# Flatcaster-Link-sch.net
KiCad netlist of a schematic drawn in Altium Designer
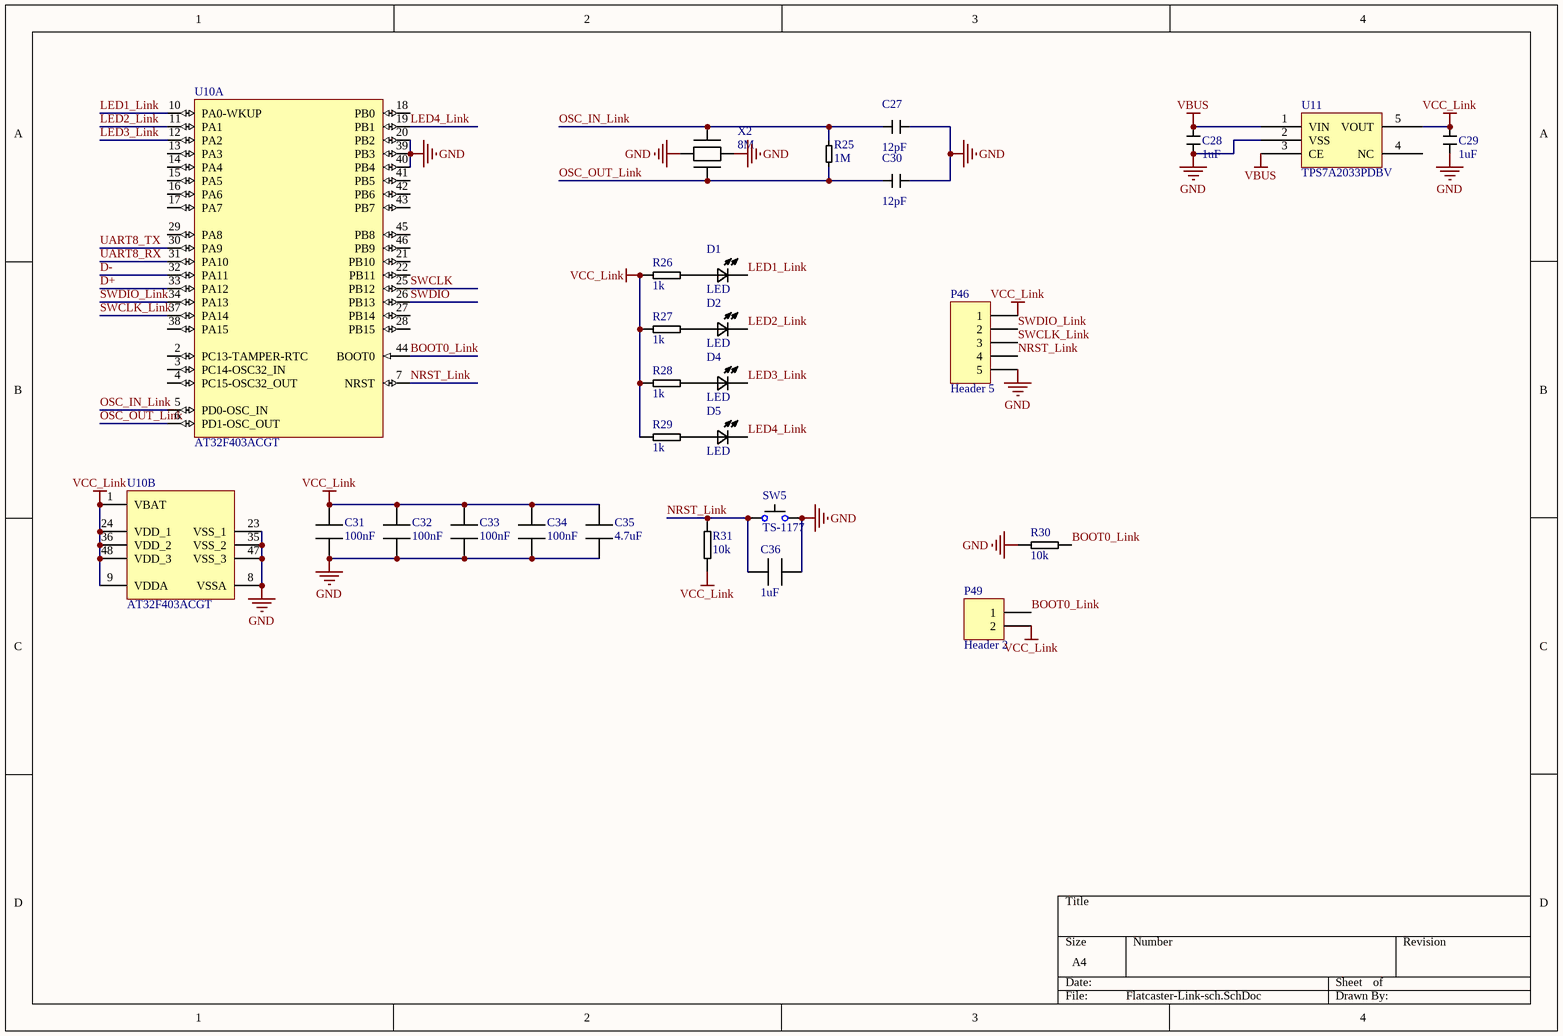
[diagram p0: Flatcaster-Link-sch.SchDoc]

(export (version "E")
  (design (tool "Eeschema 10.0.6"))
  (components
    (comp (ref "C27") (value "12pF") (footprint "0603-Cap") (libsource (lib "") (part "Cap_1")))
    (comp (ref "C28") (value "1uF") (footprint "0603-Cap") (libsource (lib "") (part "Cap_1")))
    (comp (ref "C29") (value "1uF") (footprint "0603-Cap") (libsource (lib "") (part "Cap_1")))
    (comp (ref "C30") (value "12pF") (footprint "0603-Cap") (libsource (lib "") (part "Cap_1")))
    (comp (ref "C31") (value "100nF") (footprint "0603-Cap") (libsource (lib "LibCfrpg") (part "Cap")))
    (comp (ref "C32") (value "100nF") (footprint "0603-Cap") (libsource (lib "LibCfrpg") (part "Cap")))
    (comp (ref "C33") (value "100nF") (footprint "0603-Cap") (libsource (lib "LibCfrpg") (part "Cap")))
    (comp (ref "C34") (value "100nF") (footprint "0603-Cap") (libsource (lib "LibCfrpg") (part "Cap")))
    (comp (ref "C35") (value "4.7uF") (footprint "0603-Cap") (libsource (lib "LibCfrpg") (part "Cap")))
    (comp (ref "C36") (value "1uF") (footprint "0603-Cap") (libsource (lib "LibCfrpg") (part "Cap")))
    (comp (ref "D1") (value "LED") (footprint "0603-1") (libsource (lib "LibCfrpg") (part "LED")))
    (comp (ref "D2") (value "LED") (footprint "0603-1") (libsource (lib "LibCfrpg") (part "LED")))
    (comp (ref "D4") (value "LED") (footprint "0603-1") (libsource (lib "LibCfrpg") (part "LED")))
    (comp (ref "D5") (value "LED") (footprint "0603-1") (libsource (lib "LibCfrpg") (part "LED")))
    (comp (ref "P46")
      (value "Header 5")
      (footprint "HDR1X5")
      (description "Header, 5-Pin")
      (fields (field (name "PUBLISHER") "Altium Limited"))
      (libsource (lib "Miscellaneous Connectors") (part "Header 5"))
    )
    (comp (ref "P49")
      (value "Header 2")
      (footprint "HDR1X2")
      (description "Header, 2-Pin")
      (fields (field (name "PUBLISHER") "Altium Limited"))
      (libsource (lib "Miscellaneous Connectors") (part "Header 2"))
    )
    (comp (ref "R25") (value "1M") (footprint "0603") (libsource (lib "") (part "Res_1")))
    (comp (ref "R26") (value "1k") (footprint "0603") (libsource (lib "LibCfrpg") (part "Res")))
    (comp (ref "R27") (value "1k") (footprint "0603") (libsource (lib "LibCfrpg") (part "Res")))
    (comp (ref "R28") (value "1k") (footprint "0603") (libsource (lib "LibCfrpg") (part "Res")))
    (comp (ref "R29") (value "1k") (footprint "0603") (libsource (lib "LibCfrpg") (part "Res")))
    (comp (ref "R30") (value "10k") (footprint "0603") (libsource (lib "LibCfrpg") (part "Res")))
    (comp (ref "R31") (value "10k") (footprint "0603") (libsource (lib "LibCfrpg") (part "Res")))
    (comp (ref "SW5")
      (value "TS-1177")
      (footprint "BTN3*3")
      (description "C561512")
      (libsource (lib "LibCfrpg") (part "Btn"))
    )
    (comp (ref "U10")
      (value "AT32F403ACGT")
      (footprint "STM-LQFP48_N")
      (fields (field (name "PARTNUMBER") "STM32F103CBT6"))
      (libsource (lib "STMicroelectronics STM32 F1") (part "STM32F103CBT6"))
    )
    (comp (ref "U11")
      (value "TPS7A2033PDBV")
      (footprint "SOT23-5")
      (libsource (lib "LibCfrpg") (part "ME6211"))
    )
    (comp (ref "X2")
      (value "8M")
      (footprint "XTAL-3225-4P")
      (description "C2682774")
      (libsource (lib "LibCfrpg") (part "XTAL-4LEAD"))
    )
  )
  (nets
    (net (code "1") (name "/BOOT0_Link") (class "Default")
      (node (ref "P49") (pin "1") (pinfunction "1_1") (pintype "passive"))
      (node (ref "R30") (pin "1") (pintype "passive"))
      (node (ref "U10") (pin "44") (pinfunction "BOOT0_44") (pintype "input"))
    )
    (net (code "2") (name "/D+") (class "Default")
      (node (ref "U10") (pin "33") (pinfunction "PA12_33") (pintype "bidirectional"))
    )
    (net (code "3") (name "/D-") (class "Default")
      (node (ref "U10") (pin "32") (pinfunction "PA11_32") (pintype "bidirectional"))
    )
    (net (code "4") (name "/LED1_Link") (class "Default")
      (node (ref "D1") (pin "2") (pintype "passive"))
      (node (ref "U10") (pin "10") (pinfunction "PA0-WKUP_10") (pintype "bidirectional"))
    )
    (net (code "5") (name "/LED2_Link") (class "Default")
      (node (ref "D2") (pin "2") (pintype "passive"))
      (node (ref "U10") (pin "11") (pinfunction "PA1_11") (pintype "bidirectional"))
    )
    (net (code "6") (name "/LED3_Link") (class "Default")
      (node (ref "D4") (pin "2") (pintype "passive"))
      (node (ref "U10") (pin "12") (pinfunction "PA2_12") (pintype "bidirectional"))
    )
    (net (code "7") (name "/LED4_Link") (class "Default")
      (node (ref "D5") (pin "2") (pintype "passive"))
      (node (ref "U10") (pin "19") (pinfunction "PB1_19") (pintype "bidirectional"))
    )
    (net (code "8") (name "/NRST_Link") (class "Default")
      (node (ref "C36") (pin "2") (pintype "passive"))
      (node (ref "P46") (pin "4") (pinfunction "4_4") (pintype "passive"))
      (node (ref "R31") (pin "2") (pintype "passive"))
      (node (ref "SW5") (pin "1") (pintype "passive"))
      (node (ref "U10") (pin "7") (pinfunction "NRST_7") (pintype "bidirectional"))
    )
    (net (code "9") (name "/OSC_IN_Link") (class "Default")
      (node (ref "C27") (pin "2") (pintype "passive"))
      (node (ref "R25") (pin "2") (pintype "passive"))
      (node (ref "U10") (pin "5") (pinfunction "PD0-OSC_IN_5") (pintype "bidirectional"))
      (node (ref "X2") (pin "3") (pintype "passive"))
    )
    (net (code "10") (name "/OSC_OUT_Link") (class "Default")
      (node (ref "C30") (pin "2") (pintype "passive"))
      (node (ref "R25") (pin "1") (pintype "passive"))
      (node (ref "U10") (pin "6") (pinfunction "PD1-OSC_OUT_6") (pintype "bidirectional"))
      (node (ref "X2") (pin "1") (pintype "passive"))
    )
    (net (code "11") (name "/SWCLK") (class "Default")
      (node (ref "U10") (pin "25") (pinfunction "PB12_25") (pintype "bidirectional"))
    )
    (net (code "12") (name "/SWCLK_Link") (class "Default")
      (node (ref "P46") (pin "3") (pinfunction "3_3") (pintype "passive"))
      (node (ref "U10") (pin "37") (pinfunction "PA14_37") (pintype "bidirectional"))
    )
    (net (code "13") (name "/SWDIO") (class "Default")
      (node (ref "U10") (pin "26") (pinfunction "PB13_26") (pintype "bidirectional"))
    )
    (net (code "14") (name "/SWDIO_Link") (class "Default")
      (node (ref "P46") (pin "2") (pinfunction "2_2") (pintype "passive"))
      (node (ref "U10") (pin "34") (pinfunction "PA13_34") (pintype "bidirectional"))
    )
    (net (code "15") (name "/UART8_RX") (class "Default")
      (node (ref "U10") (pin "31") (pinfunction "PA10_31") (pintype "bidirectional"))
    )
    (net (code "16") (name "/UART8_TX") (class "Default")
      (node (ref "U10") (pin "30") (pinfunction "PA9_30") (pintype "bidirectional"))
    )
    (net (code "17") (name "GND") (class "Default")
      (node (ref "C27") (pin "1") (pintype "passive"))
      (node (ref "C28") (pin "1") (pintype "passive"))
      (node (ref "C29") (pin "1") (pintype "passive"))
      (node (ref "C30") (pin "1") (pintype "passive"))
      (node (ref "C31") (pin "2") (pintype "passive"))
      (node (ref "C32") (pin "2") (pintype "passive"))
      (node (ref "C33") (pin "2") (pintype "passive"))
      (node (ref "C34") (pin "2") (pintype "passive"))
      (node (ref "C35") (pin "2") (pintype "passive"))
      (node (ref "C36") (pin "1") (pintype "passive"))
      (node (ref "P46") (pin "5") (pinfunction "5_5") (pintype "passive"))
      (node (ref "R30") (pin "2") (pintype "passive"))
      (node (ref "SW5") (pin "2") (pintype "passive"))
      (node (ref "U10") (pin "20") (pinfunction "PB2_20") (pintype "bidirectional"))
      (node (ref "U10") (pin "23") (pinfunction "VSS_1_23") (pintype "power_in"))
      (node (ref "U10") (pin "35") (pinfunction "VSS_2_35") (pintype "power_in"))
      (node (ref "U10") (pin "39") (pinfunction "PB3_39") (pintype "bidirectional"))
      (node (ref "U10") (pin "40") (pinfunction "PB4_40") (pintype "bidirectional"))
      (node (ref "U10") (pin "47") (pinfunction "VSS_3_47") (pintype "power_in"))
      (node (ref "U10") (pin "8") (pinfunction "VSSA_8") (pintype "power_in"))
      (node (ref "U11") (pin "2") (pinfunction "VSS_2") (pintype "passive"))
      (node (ref "X2") (pin "2") (pintype "passive"))
      (node (ref "X2") (pin "4") (pintype "passive"))
    )
    (net (code "18") (name "Net-(D1-Pad1)") (class "Default")
      (node (ref "D1") (pin "1") (pintype "passive"))
      (node (ref "R26") (pin "1") (pintype "passive"))
    )
    (net (code "19") (name "Net-(D2-Pad1)") (class "Default")
      (node (ref "D2") (pin "1") (pintype "passive"))
      (node (ref "R27") (pin "1") (pintype "passive"))
    )
    (net (code "20") (name "Net-(D4-Pad1)") (class "Default")
      (node (ref "D4") (pin "1") (pintype "passive"))
      (node (ref "R28") (pin "1") (pintype "passive"))
    )
    (net (code "21") (name "Net-(D5-Pad1)") (class "Default")
      (node (ref "D5") (pin "1") (pintype "passive"))
      (node (ref "R29") (pin "1") (pintype "passive"))
    )
    (net (code "22") (name "VBUS") (class "Default")
      (node (ref "C28") (pin "2") (pintype "passive"))
      (node (ref "U11") (pin "1") (pinfunction "VIN_1") (pintype "passive"))
      (node (ref "U11") (pin "3") (pinfunction "CE_3") (pintype "passive"))
    )
    (net (code "23") (name "VCC_Link") (class "Default")
      (node (ref "C29") (pin "2") (pintype "passive"))
      (node (ref "C31") (pin "1") (pintype "passive"))
      (node (ref "C32") (pin "1") (pintype "passive"))
      (node (ref "C33") (pin "1") (pintype "passive"))
      (node (ref "C34") (pin "1") (pintype "passive"))
      (node (ref "C35") (pin "1") (pintype "passive"))
      (node (ref "P46") (pin "1") (pinfunction "1_1") (pintype "passive"))
      (node (ref "P49") (pin "2") (pinfunction "2_2") (pintype "passive"))
      (node (ref "R26") (pin "2") (pintype "passive"))
      (node (ref "R27") (pin "2") (pintype "passive"))
      (node (ref "R28") (pin "2") (pintype "passive"))
      (node (ref "R29") (pin "2") (pintype "passive"))
      (node (ref "R31") (pin "1") (pintype "passive"))
      (node (ref "U10") (pin "1") (pinfunction "VBAT_1") (pintype "power_in"))
      (node (ref "U10") (pin "24") (pinfunction "VDD_1_24") (pintype "power_in"))
      (node (ref "U10") (pin "36") (pinfunction "VDD_2_36") (pintype "power_in"))
      (node (ref "U10") (pin "48") (pinfunction "VDD_3_48") (pintype "power_in"))
      (node (ref "U10") (pin "9") (pinfunction "VDDA_9") (pintype "power_in"))
      (node (ref "U11") (pin "5") (pinfunction "VOUT_5") (pintype "passive"))
    )
    (net (code "24") (name "unconnected-(U10A-PA3-Pad13)") (class "Default")
      (node (ref "U10") (pin "13") (pinfunction "PA3_13") (pintype "bidirectional"))
    )
    (net (code "25") (name "unconnected-(U10A-PA4-Pad14)") (class "Default")
      (node (ref "U10") (pin "14") (pinfunction "PA4_14") (pintype "bidirectional"))
    )
    (net (code "26") (name "unconnected-(U10A-PA5-Pad15)") (class "Default")
      (node (ref "U10") (pin "15") (pinfunction "PA5_15") (pintype "bidirectional"))
    )
    (net (code "27") (name "unconnected-(U10A-PA6-Pad16)") (class "Default")
      (node (ref "U10") (pin "16") (pinfunction "PA6_16") (pintype "bidirectional"))
    )
    (net (code "28") (name "unconnected-(U10A-PA7-Pad17)") (class "Default")
      (node (ref "U10") (pin "17") (pinfunction "PA7_17") (pintype "bidirectional"))
    )
    (net (code "29") (name "unconnected-(U10A-PA8-Pad29)") (class "Default")
      (node (ref "U10") (pin "29") (pinfunction "PA8_29") (pintype "bidirectional"))
    )
    (net (code "30") (name "unconnected-(U10A-PA15-Pad38)") (class "Default")
      (node (ref "U10") (pin "38") (pinfunction "PA15_38") (pintype "bidirectional"))
    )
    (net (code "31") (name "unconnected-(U10A-PB0-Pad18)") (class "Default")
      (node (ref "U10") (pin "18") (pinfunction "PB0_18") (pintype "bidirectional"))
    )
    (net (code "32") (name "unconnected-(U10A-PB5-Pad41)") (class "Default")
      (node (ref "U10") (pin "41") (pinfunction "PB5_41") (pintype "bidirectional"))
    )
    (net (code "33") (name "unconnected-(U10A-PB6-Pad42)") (class "Default")
      (node (ref "U10") (pin "42") (pinfunction "PB6_42") (pintype "bidirectional"))
    )
    (net (code "34") (name "unconnected-(U10A-PB7-Pad43)") (class "Default")
      (node (ref "U10") (pin "43") (pinfunction "PB7_43") (pintype "bidirectional"))
    )
    (net (code "35") (name "unconnected-(U10A-PB8-Pad45)") (class "Default")
      (node (ref "U10") (pin "45") (pinfunction "PB8_45") (pintype "bidirectional"))
    )
    (net (code "36") (name "unconnected-(U10A-PB9-Pad46)") (class "Default")
      (node (ref "U10") (pin "46") (pinfunction "PB9_46") (pintype "bidirectional"))
    )
    (net (code "37") (name "unconnected-(U10A-PB10-Pad21)") (class "Default")
      (node (ref "U10") (pin "21") (pinfunction "PB10_21") (pintype "bidirectional"))
    )
    (net (code "38") (name "unconnected-(U10A-PB11-Pad22)") (class "Default")
      (node (ref "U10") (pin "22") (pinfunction "PB11_22") (pintype "bidirectional"))
    )
    (net (code "39") (name "unconnected-(U10A-PB14-Pad27)") (class "Default")
      (node (ref "U10") (pin "27") (pinfunction "PB14_27") (pintype "bidirectional"))
    )
    (net (code "40") (name "unconnected-(U10A-PB15-Pad28)") (class "Default")
      (node (ref "U10") (pin "28") (pinfunction "PB15_28") (pintype "bidirectional"))
    )
    (net (code "41") (name "unconnected-(U10A-PC13-TAMPER-RTC-Pad2)") (class "Default")
      (node (ref "U10") (pin "2") (pinfunction "PC13-TAMPER-RTC_2") (pintype "bidirectional"))
    )
    (net (code "42") (name "unconnected-(U10A-PC14-OSC32_IN-Pad3)") (class "Default")
      (node (ref "U10") (pin "3") (pinfunction "PC14-OSC32_IN_3") (pintype "bidirectional"))
    )
    (net (code "43") (name "unconnected-(U10A-PC15-OSC32_OUT-Pad4)") (class "Default")
      (node (ref "U10") (pin "4") (pinfunction "PC15-OSC32_OUT_4") (pintype "bidirectional"))
    )
    (net (code "44") (name "unconnected-(U11-NC-Pad4)") (class "Default")
      (node (ref "U11") (pin "4") (pinfunction "NC_4") (pintype "passive"))
    )
  )
)
